# display.net
KiCad netlist of a schematic drawn in Altium Designer
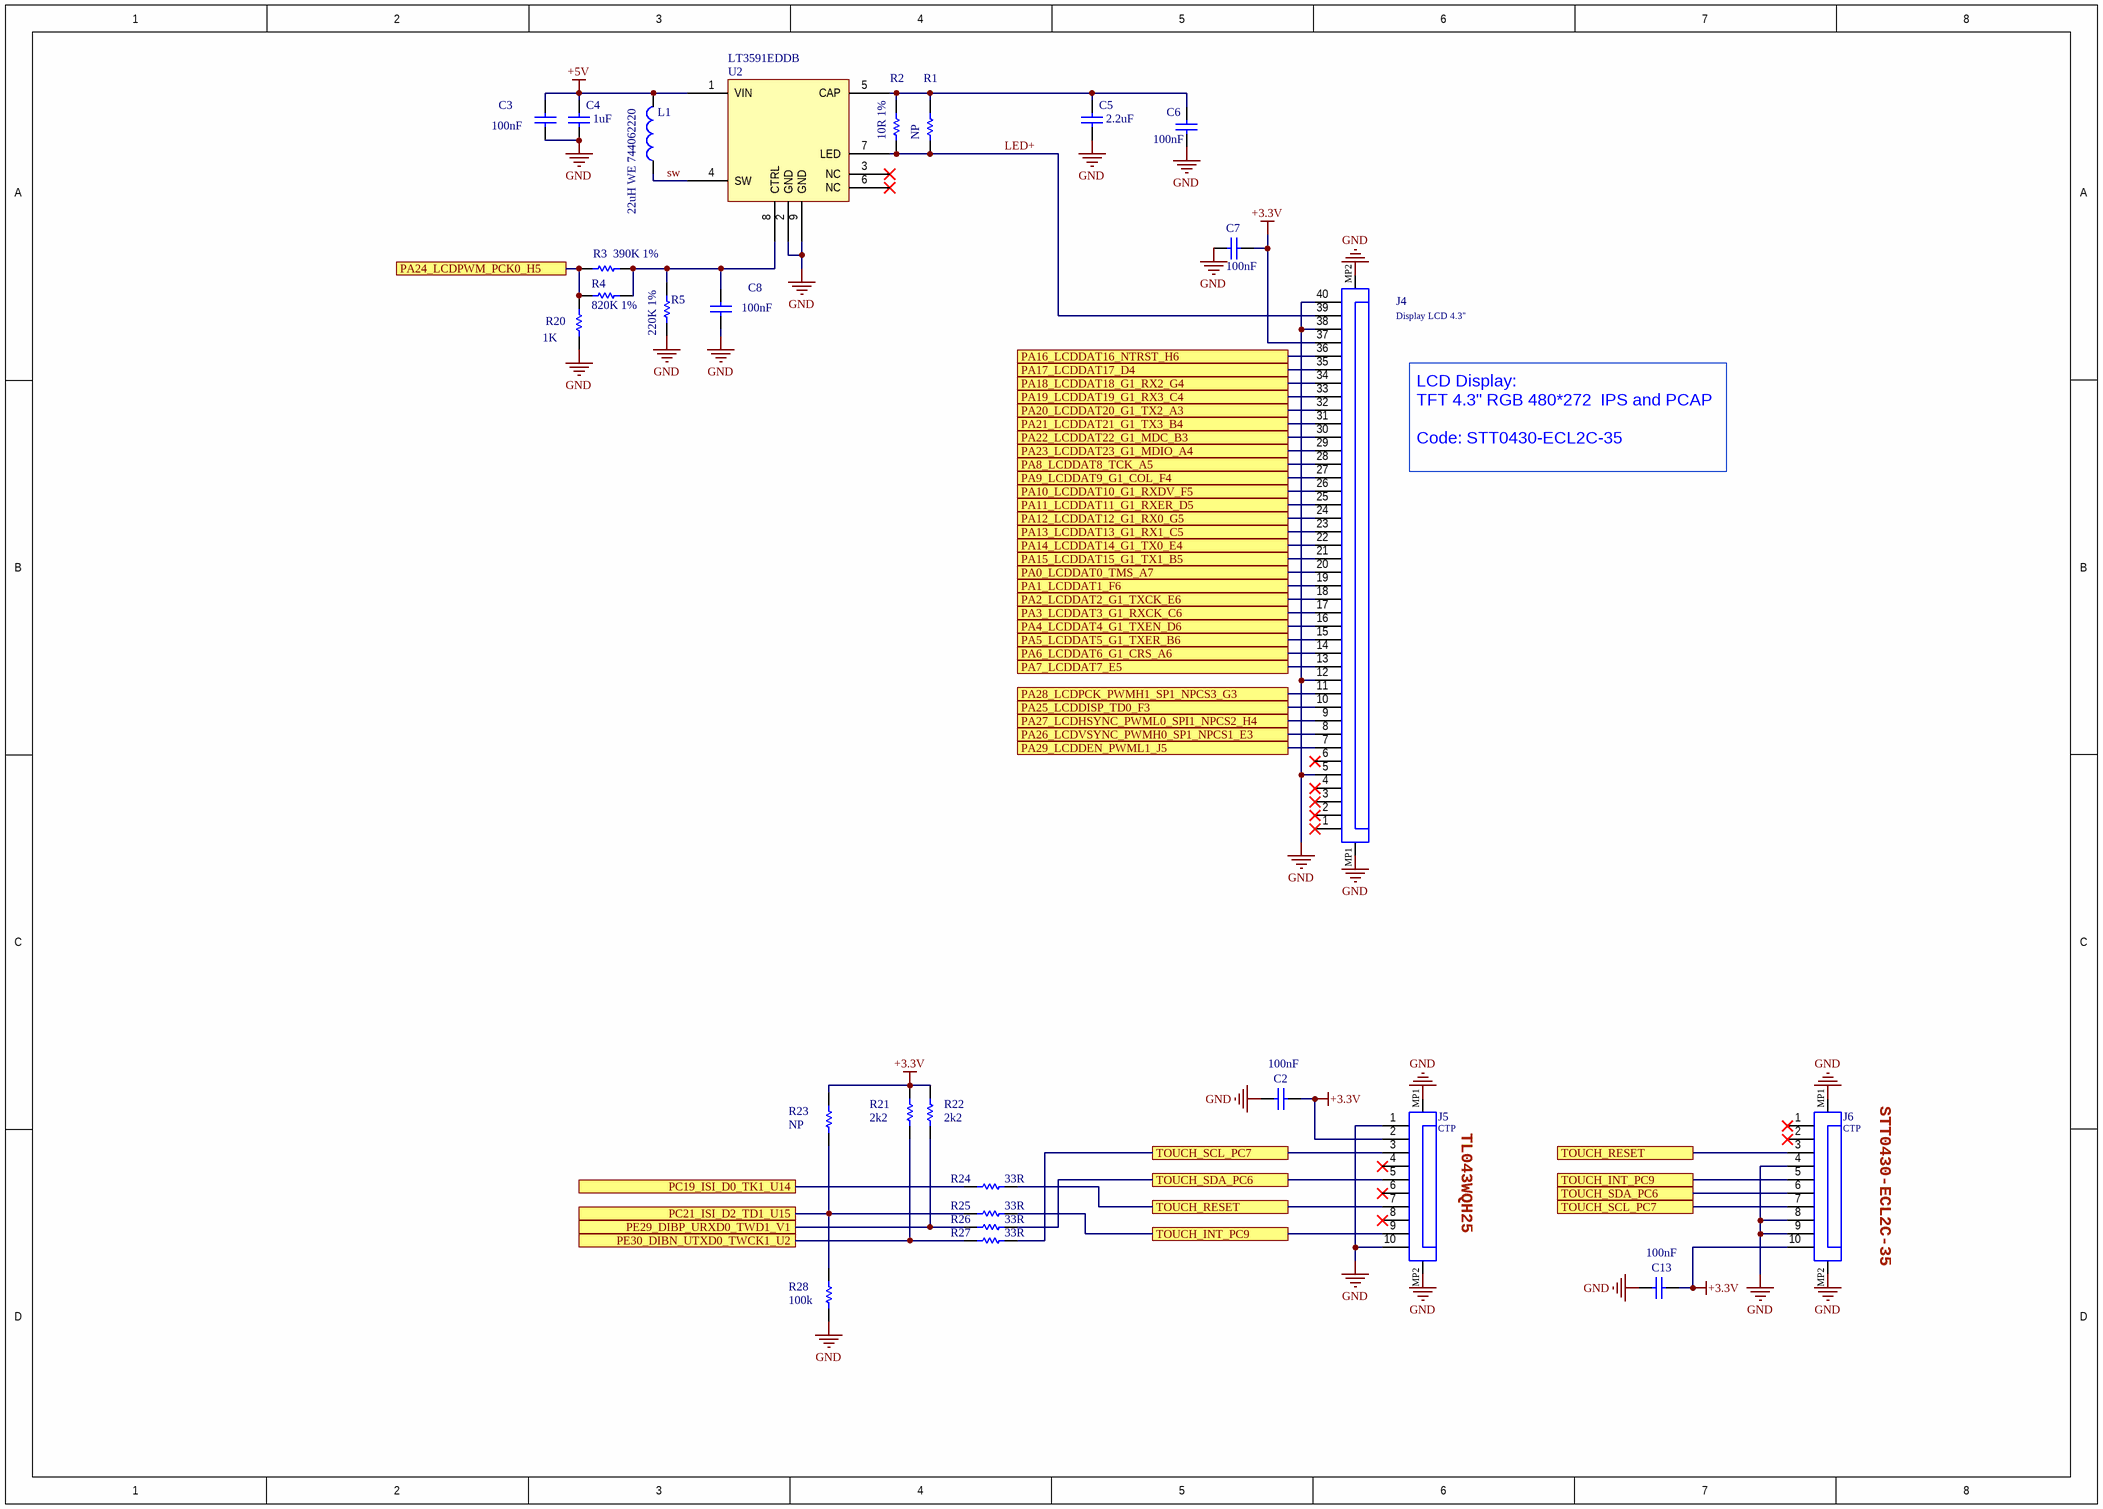
[diagram p0: display.SchDoc]

(export (version "E")
  (design (tool "Eeschema 10.0.6"))
  (components
    (comp (ref "C2")
      (value "100nF")
      (footprint "0603_[1608]")
      (description "Ceramic X7R 10V")
      (fields (field (name "PUBLISHER") "Altium Limited"))
      (libsource (lib "DEVELER_Library") (part "Cap"))
    )
    (comp (ref "C3")
      (value "100nF")
      (footprint "0603_[1608]")
      (description "Ceramic X7R 50V")
      (fields (field (name "PUBLISHER") "Altium Limited"))
      (libsource (lib "project42_lib") (part "Cap"))
    )
    (comp (ref "C4")
      (value "1uF")
      (footprint "0603_[1608]")
      (description "Ceramic X7R, X5R 16V")
      (fields (field (name "PUBLISHER") "Altium Limited"))
      (libsource (lib "project42_lib") (part "Cap"))
    )
    (comp (ref "C5")
      (value "2.2uF")
      (footprint "1210_[3225]")
      (description "Ceramic X7R, X5R 50V")
      (fields (field (name "PUBLISHER") "Altium Limited"))
      (libsource (lib "project42_lib") (part "Cap"))
    )
    (comp (ref "C6")
      (value "100nF")
      (footprint "0603_[1608]")
      (description "Ceramic X7R 50V")
      (fields (field (name "PUBLISHER") "Altium Limited"))
      (libsource (lib "project42_lib") (part "Cap"))
    )
    (comp (ref "C7")
      (value "100nF")
      (footprint "0603_[1608]")
      (description "Ceramic X5R 6.3V, 10V")
      (fields (field (name "PUBLISHER") "Altium Limited"))
      (libsource (lib "project42_lib") (part "Cap"))
    )
    (comp (ref "C8")
      (value "100nF")
      (footprint "0603_[1608]")
      (description "Ceramic X7R 50V")
      (fields (field (name "PUBLISHER") "Altium Limited"))
      (libsource (lib "project42_lib") (part "Cap"))
    )
    (comp (ref "C13")
      (value "100nF")
      (footprint "0603_[1608]")
      (description "Ceramic X7R 10V")
      (fields (field (name "PUBLISHER") "Altium Limited"))
      (libsource (lib "DEVELER_Library") (part "Cap"))
    )
    (comp (ref "J4")
      (value "Display LCD 4.3''")
      (footprint "FCC-ZIF_40PIN_0.5MM_TOP_LOWPROFILE")
      (fields (field (name "PART NUMBER") "687140183622") (field (name "PUBLISHER") "Wurth Elektronik"))
      (libsource (lib "develer_library") (part "FPC-ZIF_40PIN_1MM"))
    )
    (comp (ref "J5")
      (value "CTP")
      (footprint "FCC-ZIF_10PIN_0.5MM_LOW_PROFILE")
      (fields (field (name "PART NUMBER") "687110183722") (field (name "PUBLISHER") "Wurth Elektronik"))
      (libsource (lib "develer_library") (part "FPC-ZIF_10PIN_0.5MM"))
    )
    (comp (ref "J6")
      (value "CTP")
      (footprint "FCC-ZIF_10PIN_0.5MM_LOW_PROFILE")
      (description "Connectors, FPC, SMT ZIF, Low Profile, Horizontal, BOT Contact, pitch 0.5 mm, 10 pins (WE )")
      (fields (field (name "PART NUMBER") "687110183722") (field (name "PUBLISHER") "Wurth Elektronik"))
      (libsource (lib "develer_library") (part "FPC-ZIF_10PIN_0.5MM"))
    )
    (comp (ref "L1")
      (value "22uH WE 744062220")
      (footprint "WE-TPC-6823-X")
      (description "Power Inductor")
      (libsource (lib "DEVELER_Library") (part "Inductor"))
    )
    (comp (ref "R1")
      (value "NP")
      (footprint "0603_[1608]")
      (description "Resistor 0.125W")
      (fields (field (name "PUBLISHER") "Altium Limited"))
      (libsource (lib "project42_lib") (part "Res1"))
    )
    (comp (ref "R2")
      (value "10R 1%")
      (footprint "0603_[1608]")
      (description "Resistor 0.125W")
      (fields (field (name "PUBLISHER") "Altium Limited"))
      (libsource (lib "project42_lib") (part "Res1"))
    )
    (comp (ref "R3")
      (value "390K 1%")
      (footprint "0603_[1608]")
      (description "Resistor")
      (fields (field (name "PUBLISHER") "Altium Limited"))
      (libsource (lib "project42_lib") (part "Res1"))
    )
    (comp (ref "R4")
      (value "820K 1%")
      (footprint "0603_[1608]")
      (description "Resistor")
      (fields (field (name "PUBLISHER") "Altium Limited"))
      (libsource (lib "project42_lib") (part "Res1"))
    )
    (comp (ref "R5")
      (value "220K 1%")
      (footprint "0603_[1608]")
      (description "Resistor")
      (fields (field (name "PUBLISHER") "Altium Limited"))
      (libsource (lib "project42_lib") (part "Res1"))
    )
    (comp (ref "R20")
      (value "1K")
      (footprint "0603_[1608]")
      (description "Resistor")
      (fields (field (name "PUBLISHER") "Altium Limited"))
      (libsource (lib "project42_lib") (part "Res1"))
    )
    (comp (ref "R21")
      (value "2k2")
      (footprint "0603_[1608]")
      (description "Resistor 0.125W")
      (fields (field (name "PUBLISHER") "Altium Limited"))
      (libsource (lib "DEVELER_Library") (part "Res1"))
    )
    (comp (ref "R22")
      (value "2k2")
      (footprint "0603_[1608]")
      (description "Resistor 0.125W")
      (fields (field (name "PUBLISHER") "Altium Limited"))
      (libsource (lib "DEVELER_Library") (part "Res1"))
    )
    (comp (ref "R23")
      (value "NP")
      (footprint "0603_[1608]")
      (description "Resistor 0.125W")
      (fields (field (name "PUBLISHER") "Altium Limited"))
      (libsource (lib "DEVELER_Library") (part "Res1"))
    )
    (comp (ref "R24")
      (value "33R")
      (footprint "0603_[1608]")
      (description "Resistor")
      (fields (field (name "PUBLISHER") "Altium Limited"))
      (libsource (lib "DEVELER_Library") (part "Res1"))
    )
    (comp (ref "R25")
      (value "33R")
      (footprint "0603_[1608]")
      (description "Resistor")
      (fields (field (name "PUBLISHER") "Altium Limited"))
      (libsource (lib "DEVELER_Library") (part "Res1"))
    )
    (comp (ref "R26")
      (value "33R")
      (footprint "0603_[1608]")
      (description "Resistor")
      (fields (field (name "PUBLISHER") "Altium Limited"))
      (libsource (lib "DEVELER_Library") (part "Res1"))
    )
    (comp (ref "R27")
      (value "33R")
      (footprint "0603_[1608]")
      (description "Resistor")
      (fields (field (name "PUBLISHER") "Altium Limited"))
      (libsource (lib "DEVELER_Library") (part "Res1"))
    )
    (comp (ref "R28")
      (value "100k")
      (footprint "0603_[1608]")
      (description "Resistor 0.125W")
      (fields (field (name "PUBLISHER") "Altium Limited"))
      (libsource (lib "DEVELER_Library") (part "Res1"))
    )
    (comp (ref "U2")
      (value "LT3591EDDB")
      (footprint "PQFN50P300X200X75_HS-9L")
      (description "White LED Driver with Integrated Schottky")
      (libsource (lib "DEVELER_Library") (part "LT3591"))
    )
  )
  (nets
    (net (code "1") (name "+3.3V") (class "Default")
      (node (ref "C13") (pin "1") (pinfunction "1_1") (pintype "passive"))
      (node (ref "C2") (pin "1") (pinfunction "1_1") (pintype "passive"))
      (node (ref "C7") (pin "1") (pinfunction "1_1") (pintype "passive"))
      (node (ref "J4") (pin "37") (pinfunction "37_37") (pintype "passive"))
      (node (ref "J5") (pin "2") (pinfunction "2_2") (pintype "passive"))
      (node (ref "J6") (pin "10") (pinfunction "10_10") (pintype "passive"))
      (node (ref "R21") (pin "1") (pinfunction "1_1") (pintype "passive"))
      (node (ref "R22") (pin "1") (pinfunction "1_1") (pintype "passive"))
      (node (ref "R23") (pin "1") (pinfunction "1_1") (pintype "passive"))
    )
    (net (code "2") (name "+5V") (class "Default")
      (node (ref "C3") (pin "2") (pinfunction "2_2") (pintype "passive"))
      (node (ref "C4") (pin "2") (pinfunction "2_2") (pintype "passive"))
      (node (ref "L1") (pin "2") (pinfunction "2_2") (pintype "passive"))
      (node (ref "U2") (pin "1") (pinfunction "VIN_1") (pintype "power_in"))
    )
    (net (code "3") (name "/LED+") (class "Default")
      (node (ref "J4") (pin "39") (pinfunction "39_39") (pintype "passive"))
      (node (ref "R1") (pin "1") (pinfunction "1_1") (pintype "passive"))
      (node (ref "R2") (pin "1") (pinfunction "1_1") (pintype "passive"))
      (node (ref "U2") (pin "7") (pinfunction "LED_7") (pintype "passive"))
    )
    (net (code "4") (name "/PA0_LCDDAT0_TMS_A7") (class "Default")
      (node (ref "J4") (pin "20") (pinfunction "20_20") (pintype "passive"))
    )
    (net (code "5") (name "/PA1_LCDDAT1_F6") (class "Default")
      (node (ref "J4") (pin "19") (pinfunction "19_19") (pintype "passive"))
    )
    (net (code "6") (name "/PA2_LCDDAT2_G1_TXCK_E6") (class "Default")
      (node (ref "J4") (pin "18") (pinfunction "18_18") (pintype "passive"))
    )
    (net (code "7") (name "/PA3_LCDDAT3_G1_RXCK_C6") (class "Default")
      (node (ref "J4") (pin "17") (pinfunction "17_17") (pintype "passive"))
    )
    (net (code "8") (name "/PA4_LCDDAT4_G1_TXEN_D6") (class "Default")
      (node (ref "J4") (pin "16") (pinfunction "16_16") (pintype "passive"))
    )
    (net (code "9") (name "/PA5_LCDDAT5_G1_TXER_B6") (class "Default")
      (node (ref "J4") (pin "15") (pinfunction "15_15") (pintype "passive"))
    )
    (net (code "10") (name "/PA6_LCDDAT6_G1_CRS_A6") (class "Default")
      (node (ref "J4") (pin "14") (pinfunction "14_14") (pintype "passive"))
    )
    (net (code "11") (name "/PA7_LCDDAT7_E5") (class "Default")
      (node (ref "J4") (pin "13") (pinfunction "13_13") (pintype "passive"))
    )
    (net (code "12") (name "/PA8_LCDDAT8_TCK_A5") (class "Default")
      (node (ref "J4") (pin "28") (pinfunction "28_28") (pintype "passive"))
    )
    (net (code "13") (name "/PA9_LCDDAT9_G1_COL_F4") (class "Default")
      (node (ref "J4") (pin "27") (pinfunction "27_27") (pintype "passive"))
    )
    (net (code "14") (name "/PA10_LCDDAT10_G1_RXDV_F5") (class "Default")
      (node (ref "J4") (pin "26") (pinfunction "26_26") (pintype "passive"))
    )
    (net (code "15") (name "/PA11_LCDDAT11_G1_RXER_D5") (class "Default")
      (node (ref "J4") (pin "25") (pinfunction "25_25") (pintype "passive"))
    )
    (net (code "16") (name "/PA12_LCDDAT12_G1_RX0_G5") (class "Default")
      (node (ref "J4") (pin "24") (pinfunction "24_24") (pintype "passive"))
    )
    (net (code "17") (name "/PA13_LCDDAT13_G1_RX1_C5") (class "Default")
      (node (ref "J4") (pin "23") (pinfunction "23_23") (pintype "passive"))
    )
    (net (code "18") (name "/PA14_LCDDAT14_G1_TX0_E4") (class "Default")
      (node (ref "J4") (pin "22") (pinfunction "22_22") (pintype "passive"))
    )
    (net (code "19") (name "/PA15_LCDDAT15_G1_TX1_B5") (class "Default")
      (node (ref "J4") (pin "21") (pinfunction "21_21") (pintype "passive"))
    )
    (net (code "20") (name "/PA16_LCDDAT16_NTRST_H6") (class "Default")
      (node (ref "J4") (pin "36") (pinfunction "36_36") (pintype "passive"))
    )
    (net (code "21") (name "/PA17_LCDDAT17_D4") (class "Default")
      (node (ref "J4") (pin "35") (pinfunction "35_35") (pintype "passive"))
    )
    (net (code "22") (name "/PA18_LCDDAT18_G1_RX2_G4") (class "Default")
      (node (ref "J4") (pin "34") (pinfunction "34_34") (pintype "passive"))
    )
    (net (code "23") (name "/PA19_LCDDAT19_G1_RX3_C4") (class "Default")
      (node (ref "J4") (pin "33") (pinfunction "33_33") (pintype "passive"))
    )
    (net (code "24") (name "/PA20_LCDDAT20_G1_TX2_A3") (class "Default")
      (node (ref "J4") (pin "32") (pinfunction "32_32") (pintype "passive"))
    )
    (net (code "25") (name "/PA21_LCDDAT21_G1_TX3_B4") (class "Default")
      (node (ref "J4") (pin "31") (pinfunction "31_31") (pintype "passive"))
    )
    (net (code "26") (name "/PA22_LCDDAT22_G1_MDC_B3") (class "Default")
      (node (ref "J4") (pin "30") (pinfunction "30_30") (pintype "passive"))
    )
    (net (code "27") (name "/PA23_LCDDAT23_G1_MDIO_A4") (class "Default")
      (node (ref "J4") (pin "29") (pinfunction "29_29") (pintype "passive"))
    )
    (net (code "28") (name "/PA24_LCDPWM_PCK0_H5") (class "Default")
      (node (ref "R20") (pin "1") (pinfunction "1_1") (pintype "passive"))
      (node (ref "R3") (pin "2") (pinfunction "2_2") (pintype "passive"))
      (node (ref "R4") (pin "1") (pinfunction "1_1") (pintype "passive"))
    )
    (net (code "29") (name "/PA25_LCDDISP_TD0_F3") (class "Default")
      (node (ref "J4") (pin "10") (pinfunction "10_10") (pintype "passive"))
    )
    (net (code "30") (name "/PA26_LCDVSYNC_PWMH0_SP1_NPCS1_E3") (class "Default")
      (node (ref "J4") (pin "8") (pinfunction "8_8") (pintype "passive"))
    )
    (net (code "31") (name "/PA27_LCDHSYNC_PWML0_SPI1_NPCS2_H4") (class "Default")
      (node (ref "J4") (pin "9") (pinfunction "9_9") (pintype "passive"))
    )
    (net (code "32") (name "/PA28_LCDPCK_PWMH1_SP1_NPCS3_G3") (class "Default")
      (node (ref "J4") (pin "11") (pinfunction "11_11") (pintype "passive"))
    )
    (net (code "33") (name "/PA29_LCDDEN_PWML1_J5") (class "Default")
      (node (ref "J4") (pin "7") (pinfunction "7_7") (pintype "passive"))
    )
    (net (code "34") (name "/PC19_ISI_D0_TK1_U14") (class "Default")
      (node (ref "R24") (pin "2") (pinfunction "2_2") (pintype "passive"))
    )
    (net (code "35") (name "/PC21_ISI_D2_TD1_U15") (class "Default")
      (node (ref "R23") (pin "2") (pinfunction "2_2") (pintype "passive"))
      (node (ref "R25") (pin "2") (pinfunction "2_2") (pintype "passive"))
      (node (ref "R28") (pin "1") (pinfunction "1_1") (pintype "passive"))
    )
    (net (code "36") (name "/PE29_DIBP_URXD0_TWD1_V1") (class "Default")
      (node (ref "R22") (pin "2") (pinfunction "2_2") (pintype "passive"))
      (node (ref "R26") (pin "2") (pinfunction "2_2") (pintype "passive"))
    )
    (net (code "37") (name "/PE30_DIBN_UTXD0_TWCK1_U2") (class "Default")
      (node (ref "R21") (pin "2") (pinfunction "2_2") (pintype "passive"))
      (node (ref "R27") (pin "2") (pinfunction "2_2") (pintype "passive"))
    )
    (net (code "38") (name "/TOUCH_INT_PC9") (class "Default")
      (node (ref "J5") (pin "9") (pinfunction "9_9") (pintype "passive"))
      (node (ref "J6") (pin "5") (pinfunction "5_5") (pintype "passive"))
      (node (ref "R25") (pin "1") (pinfunction "1_1") (pintype "passive"))
    )
    (net (code "39") (name "/TOUCH_RESET") (class "Default")
      (node (ref "J5") (pin "7") (pinfunction "7_7") (pintype "passive"))
      (node (ref "J6") (pin "3") (pinfunction "3_3") (pintype "passive"))
      (node (ref "R24") (pin "1") (pinfunction "1_1") (pintype "passive"))
    )
    (net (code "40") (name "/TOUCH_SCL_PC7") (class "Default")
      (node (ref "J5") (pin "3") (pinfunction "3_3") (pintype "passive"))
      (node (ref "J6") (pin "7") (pinfunction "7_7") (pintype "passive"))
      (node (ref "R27") (pin "1") (pinfunction "1_1") (pintype "passive"))
    )
    (net (code "41") (name "/TOUCH_SDA_PC6") (class "Default")
      (node (ref "J5") (pin "5") (pinfunction "5_5") (pintype "passive"))
      (node (ref "J6") (pin "6") (pinfunction "6_6") (pintype "passive"))
      (node (ref "R26") (pin "1") (pinfunction "1_1") (pintype "passive"))
    )
    (net (code "42") (name "/sw") (class "Default")
      (node (ref "L1") (pin "1") (pinfunction "1_1") (pintype "passive"))
      (node (ref "U2") (pin "4") (pinfunction "SW_4") (pintype "passive"))
    )
    (net (code "43") (name "GND") (class "Default")
      (node (ref "C13") (pin "2") (pinfunction "2_2") (pintype "passive"))
      (node (ref "C2") (pin "2") (pinfunction "2_2") (pintype "passive"))
      (node (ref "C3") (pin "1") (pinfunction "1_1") (pintype "passive"))
      (node (ref "C4") (pin "1") (pinfunction "1_1") (pintype "passive"))
      (node (ref "C5") (pin "1") (pinfunction "1_1") (pintype "passive"))
      (node (ref "C6") (pin "1") (pinfunction "1_1") (pintype "passive"))
      (node (ref "C7") (pin "2") (pinfunction "2_2") (pintype "passive"))
      (node (ref "C8") (pin "1") (pinfunction "1_1") (pintype "passive"))
      (node (ref "J4") (pin "12") (pinfunction "12_12") (pintype "passive"))
      (node (ref "J4") (pin "38") (pinfunction "38_38") (pintype "passive"))
      (node (ref "J4") (pin "40") (pinfunction "40_40") (pintype "passive"))
      (node (ref "J4") (pin "5") (pinfunction "5_5") (pintype "passive"))
      (node (ref "J4") (pin "MP1") (pinfunction "MP1_MP1") (pintype "passive"))
      (node (ref "J4") (pin "MP2") (pinfunction "MP2_MP2") (pintype "passive"))
      (node (ref "J5") (pin "1") (pinfunction "1_1") (pintype "passive"))
      (node (ref "J5") (pin "10") (pinfunction "10_10") (pintype "passive"))
      (node (ref "J5") (pin "MP1") (pinfunction "MP1_MP1") (pintype "passive"))
      (node (ref "J5") (pin "MP2") (pinfunction "MP2_MP2") (pintype "passive"))
      (node (ref "J6") (pin "4") (pinfunction "4_4") (pintype "passive"))
      (node (ref "J6") (pin "8") (pinfunction "8_8") (pintype "passive"))
      (node (ref "J6") (pin "9") (pinfunction "9_9") (pintype "passive"))
      (node (ref "J6") (pin "MP1") (pinfunction "MP1_MP1") (pintype "passive"))
      (node (ref "J6") (pin "MP2") (pinfunction "MP2_MP2") (pintype "passive"))
      (node (ref "R20") (pin "2") (pinfunction "2_2") (pintype "passive"))
      (node (ref "R28") (pin "2") (pinfunction "2_2") (pintype "passive"))
      (node (ref "R5") (pin "2") (pinfunction "2_2") (pintype "passive"))
      (node (ref "U2") (pin "2") (pinfunction "GND_2") (pintype "power_in"))
      (node (ref "U2") (pin "9") (pinfunction "GND_9") (pintype "power_in"))
    )
    (net (code "44") (name "Net-(U2-CAP)") (class "Default")
      (node (ref "C5") (pin "2") (pinfunction "2_2") (pintype "passive"))
      (node (ref "C6") (pin "2") (pinfunction "2_2") (pintype "passive"))
      (node (ref "R1") (pin "2") (pinfunction "2_2") (pintype "passive"))
      (node (ref "R2") (pin "2") (pinfunction "2_2") (pintype "passive"))
      (node (ref "U2") (pin "5") (pinfunction "CAP_5") (pintype "passive"))
    )
    (net (code "45") (name "Net-(U2-CTRL)") (class "Default")
      (node (ref "C8") (pin "2") (pinfunction "2_2") (pintype "passive"))
      (node (ref "R3") (pin "1") (pinfunction "1_1") (pintype "passive"))
      (node (ref "R4") (pin "2") (pinfunction "2_2") (pintype "passive"))
      (node (ref "R5") (pin "1") (pinfunction "1_1") (pintype "passive"))
      (node (ref "U2") (pin "8") (pinfunction "CTRL_8") (pintype "passive"))
    )
    (net (code "46") (name "unconnected-(J4-Pad1)") (class "Default")
      (node (ref "J4") (pin "1") (pinfunction "1_1") (pintype "passive+no_connect"))
    )
    (net (code "47") (name "unconnected-(J4-Pad2)") (class "Default")
      (node (ref "J4") (pin "2") (pinfunction "2_2") (pintype "passive+no_connect"))
    )
    (net (code "48") (name "unconnected-(J4-Pad3)") (class "Default")
      (node (ref "J4") (pin "3") (pinfunction "3_3") (pintype "passive+no_connect"))
    )
    (net (code "49") (name "unconnected-(J4-Pad4)") (class "Default")
      (node (ref "J4") (pin "4") (pinfunction "4_4") (pintype "passive+no_connect"))
    )
    (net (code "50") (name "unconnected-(J4-Pad6)") (class "Default")
      (node (ref "J4") (pin "6") (pinfunction "6_6") (pintype "passive+no_connect"))
    )
    (net (code "51") (name "unconnected-(J5-Pad4)") (class "Default")
      (node (ref "J5") (pin "4") (pinfunction "4_4") (pintype "passive+no_connect"))
    )
    (net (code "52") (name "unconnected-(J5-Pad6)") (class "Default")
      (node (ref "J5") (pin "6") (pinfunction "6_6") (pintype "passive+no_connect"))
    )
    (net (code "53") (name "unconnected-(J5-Pad8)") (class "Default")
      (node (ref "J5") (pin "8") (pinfunction "8_8") (pintype "passive+no_connect"))
    )
    (net (code "54") (name "unconnected-(J6-Pad1)") (class "Default")
      (node (ref "J6") (pin "1") (pinfunction "1_1") (pintype "passive+no_connect"))
    )
    (net (code "55") (name "unconnected-(J6-Pad2)") (class "Default")
      (node (ref "J6") (pin "2") (pinfunction "2_2") (pintype "passive+no_connect"))
    )
    (net (code "56") (name "unconnected-(U2-NC-Pad3)") (class "Default")
      (node (ref "U2") (pin "3") (pinfunction "NC_3") (pintype "passive+no_connect"))
    )
    (net (code "57") (name "unconnected-(U2-NC-Pad6)") (class "Default")
      (node (ref "U2") (pin "6") (pinfunction "NC_6") (pintype "passive+no_connect"))
    )
  )
)
